# USGlasses.net
KiCad netlist of a schematic drawn in EAGLE
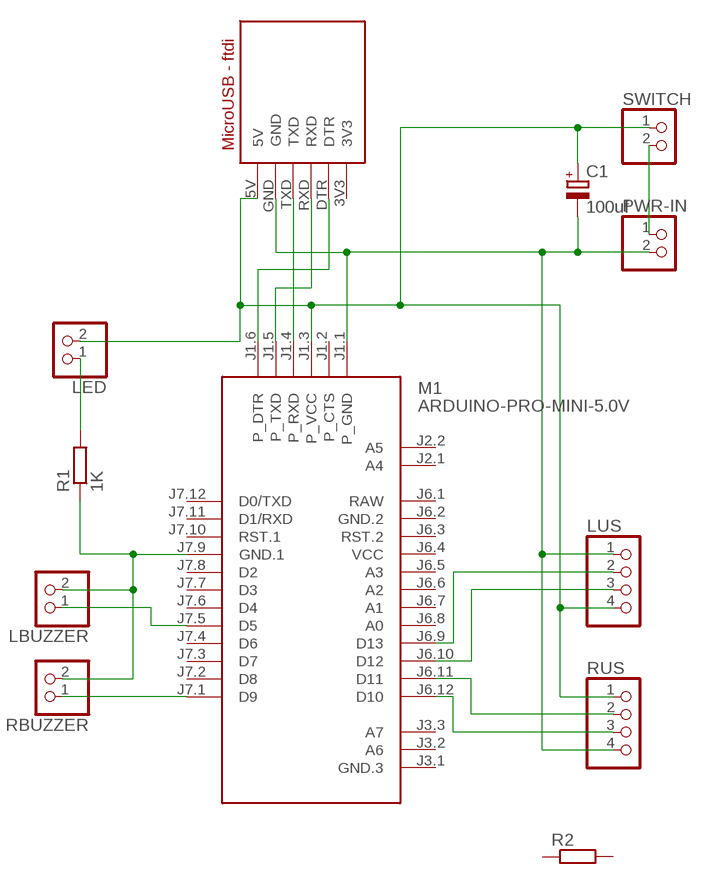
[diagram p0: schematic, sheet 1]

(export (version "E")
  (design (tool "Eeschema 10.0.6"))
  (components
    (comp (ref "C1")
      (value "100uf")
      (footprint "eagle-import:E2,5-6E")
      (libsource (lib "eagle-import") (part "CPOL-EUE2,5-6E"))
    )
    (comp (ref "LBUZZER")
      (value "PINHD-1X2")
      (footprint "eagle-import:1X02")
      (libsource (lib "eagle-import") (part "PINHD-1X2"))
    )
    (comp (ref "LED")
      (value "PINHD-1X2")
      (footprint "eagle-import:1X02")
      (libsource (lib "eagle-import") (part "PINHD-1X2"))
    )
    (comp (ref "LUS")
      (value "PINHD-1X4")
      (footprint "eagle-import:1X04")
      (libsource (lib "eagle-import") (part "PINHD-1X4"))
    )
    (comp (ref "M1")
      (value "ARDUINO-PRO-MINI-5.0V")
      (footprint "eagle-import:ARDUINO-PRO-MINI")
      (libsource (lib "eagle-import") (part "ARDUINO-PRO-MINI-5.0V"))
    )
    (comp (ref "PWR-IN")
      (value "PINHD-1X2")
      (footprint "eagle-import:1X02")
      (libsource (lib "eagle-import") (part "PINHD-1X2"))
    )
    (comp (ref "R1")
      (value "1K")
      (footprint "eagle-import:0204_7")
      (libsource (lib "eagle-import") (part "R-EU_0204/7"))
    )
    (comp (ref "R2")
      (value "R-EU_0204/7")
      (footprint "eagle-import:0204_7")
      (libsource (lib "eagle-import") (part "R-EU_0204/7"))
    )
    (comp (ref "RBUZZER")
      (value "PINHD-1X2")
      (footprint "eagle-import:1X02")
      (libsource (lib "eagle-import") (part "PINHD-1X2"))
    )
    (comp (ref "RUS")
      (value "PINHD-1X4")
      (footprint "eagle-import:1X04")
      (libsource (lib "eagle-import") (part "PINHD-1X4"))
    )
    (comp (ref "SWITCH")
      (value "PINHD-1X2")
      (footprint "eagle-import:1X02")
      (libsource (lib "eagle-import") (part "PINHD-1X2"))
    )
    (comp (ref "U$1")
      (value "MICRO-USB-DEV")
      (footprint "eagle-import:MICRO-USB-PAC")
      (libsource (lib "eagle-import") (part "MICRO-USB-DEV"))
    )
  )
  (nets
    (net (code "1") (name "/3V3") (class "Default")
      (node (ref "U$1") (pin "3V3") (pinfunction "3V3_3V3") (pintype "power_in"))
    )
    (net (code "2") (name "/GND.2") (class "Default")
      (node (ref "M1") (pin "J6.2") (pinfunction "GND.2_J6.2") (pintype "power_in"))
    )
    (net (code "3") (name "/RAW") (class "Default")
      (node (ref "M1") (pin "J6.1") (pinfunction "RAW_J6.1") (pintype "power_in"))
    )
    (net (code "4") (name "/VCC") (class "Default")
      (node (ref "M1") (pin "J6.4") (pinfunction "VCC_J6.4") (pintype "power_in"))
    )
    (net (code "5") (name "Net-(LED-Pad1)") (class "Default")
      (node (ref "LED") (pin "1") (pinfunction "1_1") (pintype "passive"))
      (node (ref "R1") (pin "2") (pinfunction "2_2") (pintype "passive"))
    )
    (net (code "6") (name "Net-(M1-D5)") (class "Default")
      (node (ref "LBUZZER") (pin "1") (pinfunction "1_1") (pintype "passive"))
      (node (ref "M1") (pin "J7.5") (pinfunction "D5_J7.5") (pintype "bidirectional"))
    )
    (net (code "7") (name "Net-(M1-D9)") (class "Default")
      (node (ref "M1") (pin "J7.1") (pinfunction "D9_J7.1") (pintype "bidirectional"))
      (node (ref "RBUZZER") (pin "1") (pinfunction "1_1") (pintype "passive"))
    )
    (net (code "8") (name "Net-(M1-D10)") (class "Default")
      (node (ref "M1") (pin "J6.12") (pinfunction "D10_J6.12") (pintype "bidirectional"))
      (node (ref "RUS") (pin "3") (pinfunction "3_3") (pintype "passive"))
    )
    (net (code "9") (name "Net-(M1-D11)") (class "Default")
      (node (ref "M1") (pin "J6.11") (pinfunction "D11_J6.11") (pintype "bidirectional"))
      (node (ref "RUS") (pin "2") (pinfunction "2_2") (pintype "passive"))
    )
    (net (code "10") (name "Net-(M1-D12)") (class "Default")
      (node (ref "LUS") (pin "3") (pinfunction "3_3") (pintype "passive"))
      (node (ref "M1") (pin "J6.10") (pinfunction "D12_J6.10") (pintype "bidirectional"))
    )
    (net (code "11") (name "Net-(M1-D13)") (class "Default")
      (node (ref "LUS") (pin "2") (pinfunction "2_2") (pintype "passive"))
      (node (ref "M1") (pin "J6.9") (pinfunction "D13_J6.9") (pintype "bidirectional"))
    )
    (net (code "12") (name "Net-(M1-GND.1)") (class "Default")
      (node (ref "LBUZZER") (pin "2") (pinfunction "2_2") (pintype "passive"))
      (node (ref "M1") (pin "J7.9") (pinfunction "GND.1_J7.9") (pintype "power_in"))
      (node (ref "R1") (pin "1") (pinfunction "1_1") (pintype "passive"))
      (node (ref "RBUZZER") (pin "2") (pinfunction "2_2") (pintype "passive"))
    )
    (net (code "13") (name "Net-(M1-P_DTR)") (class "Default")
      (node (ref "M1") (pin "J1.6") (pinfunction "P_DTR_J1.6") (pintype "bidirectional"))
      (node (ref "U$1") (pin "DTR") (pinfunction "DTR_DTR") (pintype "power_in"))
    )
    (net (code "14") (name "Net-(M1-P_GND)") (class "Default")
      (node (ref "C1") (pin "-") (pinfunction "-_-") (pintype "passive"))
      (node (ref "LUS") (pin "1") (pinfunction "1_1") (pintype "passive"))
      (node (ref "M1") (pin "J1.1") (pinfunction "P_GND_J1.1") (pintype "bidirectional"))
      (node (ref "PWR-IN") (pin "2") (pinfunction "2_2") (pintype "passive"))
      (node (ref "RUS") (pin "4") (pinfunction "4_4") (pintype "passive"))
      (node (ref "U$1") (pin "GND") (pinfunction "GND_GND") (pintype "bidirectional"))
    )
    (net (code "15") (name "Net-(M1-P_RXD)") (class "Default")
      (node (ref "M1") (pin "J1.4") (pinfunction "P_RXD_J1.4") (pintype "bidirectional"))
      (node (ref "U$1") (pin "TXD") (pinfunction "TXD_TXD") (pintype "bidirectional"))
    )
    (net (code "16") (name "Net-(M1-P_TXD)") (class "Default")
      (node (ref "M1") (pin "J1.5") (pinfunction "P_TXD_J1.5") (pintype "bidirectional"))
      (node (ref "U$1") (pin "RXD") (pinfunction "RXD_RXD") (pintype "bidirectional"))
    )
    (net (code "17") (name "Net-(M1-P_VCC)") (class "Default")
      (node (ref "C1") (pin "+") (pinfunction "+_+") (pintype "passive"))
      (node (ref "LED") (pin "2") (pinfunction "2_2") (pintype "passive"))
      (node (ref "LUS") (pin "4") (pinfunction "4_4") (pintype "passive"))
      (node (ref "M1") (pin "J1.3") (pinfunction "P_VCC_J1.3") (pintype "bidirectional"))
      (node (ref "RUS") (pin "1") (pinfunction "1_1") (pintype "passive"))
      (node (ref "SWITCH") (pin "1") (pinfunction "1_1") (pintype "passive"))
      (node (ref "U$1") (pin "5V") (pinfunction "5V_5V") (pintype "power_in"))
    )
    (net (code "18") (name "Net-(PWR-IN-Pad1)") (class "Default")
      (node (ref "PWR-IN") (pin "1") (pinfunction "1_1") (pintype "passive"))
      (node (ref "SWITCH") (pin "2") (pinfunction "2_2") (pintype "passive"))
    )
    (net (code "19") (name "unconnected-(M1-A0-PadJ6.8)") (class "Default")
      (node (ref "M1") (pin "J6.8") (pinfunction "A0_J6.8") (pintype "bidirectional"))
    )
    (net (code "20") (name "unconnected-(M1-A1-PadJ6.7)") (class "Default")
      (node (ref "M1") (pin "J6.7") (pinfunction "A1_J6.7") (pintype "bidirectional"))
    )
    (net (code "21") (name "unconnected-(M1-A2-PadJ6.6)") (class "Default")
      (node (ref "M1") (pin "J6.6") (pinfunction "A2_J6.6") (pintype "bidirectional"))
    )
    (net (code "22") (name "unconnected-(M1-A3-PadJ6.5)") (class "Default")
      (node (ref "M1") (pin "J6.5") (pinfunction "A3_J6.5") (pintype "bidirectional"))
    )
    (net (code "23") (name "unconnected-(M1-A4-PadJ2.1)") (class "Default")
      (node (ref "M1") (pin "J2.1") (pinfunction "A4_J2.1") (pintype "bidirectional"))
    )
    (net (code "24") (name "unconnected-(M1-A5-PadJ2.2)") (class "Default")
      (node (ref "M1") (pin "J2.2") (pinfunction "A5_J2.2") (pintype "bidirectional"))
    )
    (net (code "25") (name "unconnected-(M1-A6-PadJ3.2)") (class "Default")
      (node (ref "M1") (pin "J3.2") (pinfunction "A6_J3.2") (pintype "bidirectional"))
    )
    (net (code "26") (name "unconnected-(M1-A7-PadJ3.3)") (class "Default")
      (node (ref "M1") (pin "J3.3") (pinfunction "A7_J3.3") (pintype "bidirectional"))
    )
    (net (code "27") (name "unconnected-(M1-D0{slash}TXD-PadJ7.12)") (class "Default")
      (node (ref "M1") (pin "J7.12") (pinfunction "D0/TXD_J7.12") (pintype "bidirectional"))
    )
    (net (code "28") (name "unconnected-(M1-D1{slash}RXD-PadJ7.11)") (class "Default")
      (node (ref "M1") (pin "J7.11") (pinfunction "D1/RXD_J7.11") (pintype "bidirectional"))
    )
    (net (code "29") (name "unconnected-(M1-D2-PadJ7.8)") (class "Default")
      (node (ref "M1") (pin "J7.8") (pinfunction "D2_J7.8") (pintype "bidirectional"))
    )
    (net (code "30") (name "unconnected-(M1-D3-PadJ7.7)") (class "Default")
      (node (ref "M1") (pin "J7.7") (pinfunction "D3_J7.7") (pintype "bidirectional"))
    )
    (net (code "31") (name "unconnected-(M1-D4-PadJ7.6)") (class "Default")
      (node (ref "M1") (pin "J7.6") (pinfunction "D4_J7.6") (pintype "bidirectional"))
    )
    (net (code "32") (name "unconnected-(M1-D6-PadJ7.4)") (class "Default")
      (node (ref "M1") (pin "J7.4") (pinfunction "D6_J7.4") (pintype "bidirectional"))
    )
    (net (code "33") (name "unconnected-(M1-D7-PadJ7.3)") (class "Default")
      (node (ref "M1") (pin "J7.3") (pinfunction "D7_J7.3") (pintype "bidirectional"))
    )
    (net (code "34") (name "unconnected-(M1-D8-PadJ7.2)") (class "Default")
      (node (ref "M1") (pin "J7.2") (pinfunction "D8_J7.2") (pintype "bidirectional"))
    )
    (net (code "35") (name "unconnected-(M1-GND.3-PadJ3.1)") (class "Default")
      (node (ref "M1") (pin "J3.1") (pinfunction "GND.3_J3.1") (pintype "bidirectional"))
    )
    (net (code "36") (name "unconnected-(M1-P_CTS-PadJ1.2)") (class "Default")
      (node (ref "M1") (pin "J1.2") (pinfunction "P_CTS_J1.2") (pintype "bidirectional"))
    )
    (net (code "37") (name "unconnected-(M1-RST.1-PadJ7.10)") (class "Default")
      (node (ref "M1") (pin "J7.10") (pinfunction "RST.1_J7.10") (pintype "bidirectional"))
    )
    (net (code "38") (name "unconnected-(M1-RST.2-PadJ6.3)") (class "Default")
      (node (ref "M1") (pin "J6.3") (pinfunction "RST.2_J6.3") (pintype "bidirectional"))
    )
    (net (code "39") (name "unconnected-(R2-Pad1)") (class "Default")
      (node (ref "R2") (pin "1") (pinfunction "1_1") (pintype "passive"))
    )
    (net (code "40") (name "unconnected-(R2-Pad2)") (class "Default")
      (node (ref "R2") (pin "2") (pinfunction "2_2") (pintype "passive"))
    )
  )
)
